# ESPExtra-0_1_1.net
KiCad netlist of a schematic drawn in EAGLE
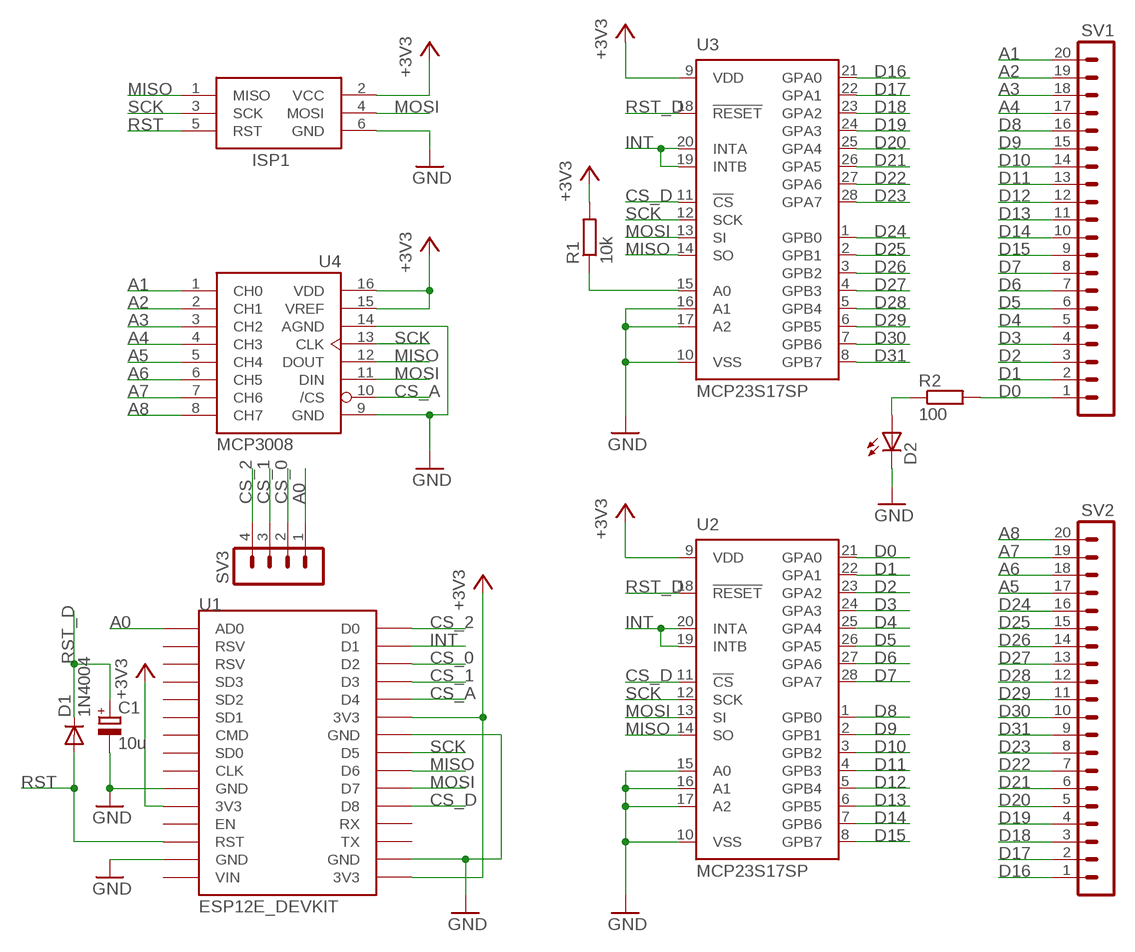
[diagram p0: schematic, sheet 1]

(export (version "E")
  (design (tool "Eeschema 10.0.6"))
  (components
    (comp (ref "C1")
      (value "10u")
      (footprint "eagle-import:E2,5-5")
      (libsource (lib "eagle-import") (part "CPOL-EUE2.5-5"))
    )
    (comp (ref "D1")
      (value "1N4004")
      (footprint "eagle-import:DO41-10")
      (libsource (lib "eagle-import") (part "1N4004"))
    )
    (comp (ref "D2")
      (value "LED3MM")
      (footprint "eagle-import:LED3MM")
      (libsource (lib "eagle-import") (part "LED3MM"))
    )
    (comp (ref "ISP1")
      (value "AVRISP-6")
      (footprint "eagle-import:AVRISP")
      (libsource (lib "eagle-import") (part "AVRISP-6"))
    )
    (comp (ref "R1")
      (value "10k")
      (footprint "eagle-import:0204_5")
      (libsource (lib "eagle-import") (part "R-EU_0204/5"))
    )
    (comp (ref "R2")
      (value "100")
      (footprint "eagle-import:0204_5")
      (libsource (lib "eagle-import") (part "R-EU_0204/5"))
    )
    (comp (ref "SV1")
      (value "MA20-1")
      (footprint "eagle-import:MA20-1")
      (libsource (lib "eagle-import") (part "MA20-1"))
    )
    (comp (ref "SV2")
      (value "MA20-1")
      (footprint "eagle-import:MA20-1")
      (libsource (lib "eagle-import") (part "MA20-1"))
    )
    (comp (ref "SV3")
      (value "MA04-1")
      (footprint "eagle-import:MA04-1")
      (libsource (lib "eagle-import") (part "MA04-1"))
    )
    (comp (ref "U1")
      (value "ESP12E_DEVKIT")
      (footprint "eagle-import:ESP12E_DEVKIT")
      (libsource (lib "eagle-import") (part "ESP12E_DEVKIT"))
    )
    (comp (ref "U2")
      (value "MCP23S17SP")
      (footprint "eagle-import:DIL28-3")
      (fields (field (name "MF") "MICROCHIP") (field (name "MPN") "MCP23S17-E/SP"))
      (libsource (lib "eagle-import") (part "MCP23S17SP"))
    )
    (comp (ref "U3")
      (value "MCP23S17SP")
      (footprint "eagle-import:DIL28-3")
      (fields (field (name "MF") "MICROCHIP") (field (name "MPN") "MCP23S17-E/SP"))
      (libsource (lib "eagle-import") (part "MCP23S17SP"))
    )
    (comp (ref "U4")
      (value "MCP3008")
      (footprint "eagle-import:DIL16")
      (libsource (lib "eagle-import") (part "MCP3008"))
    )
  )
  (nets
    (net (code "1") (name "+3V3") (class "Default")
      (node (ref "ISP1") (pin "2") (pinfunction "VCC_2") (pintype "power_in"))
      (node (ref "R1") (pin "2") (pinfunction "2_2") (pintype "passive"))
      (node (ref "U1") (pin "3V3@0") (pinfunction "3V3_3V3@0") (pintype "bidirectional"))
      (node (ref "U1") (pin "3V3@1") (pinfunction "3V3_3V3@1") (pintype "bidirectional"))
      (node (ref "U1") (pin "3V3@2") (pinfunction "3V3_3V3@2") (pintype "bidirectional"))
      (node (ref "U2") (pin "9") (pinfunction "VDD_9") (pintype "power_in"))
      (node (ref "U3") (pin "9") (pinfunction "VDD_9") (pintype "power_in"))
      (node (ref "U4") (pin "15") (pinfunction "VREF_15") (pintype "input"))
      (node (ref "U4") (pin "16") (pinfunction "VDD_16") (pintype "power_in"))
    )
    (net (code "2") (name "/A0") (class "Default")
      (node (ref "SV3") (pin "1") (pinfunction "1_1") (pintype "passive"))
      (node (ref "U1") (pin "AD0") (pinfunction "AD0_AD0") (pintype "bidirectional"))
    )
    (net (code "3") (name "/A1") (class "Default")
      (node (ref "SV1") (pin "20") (pinfunction "20_20") (pintype "passive"))
      (node (ref "U4") (pin "1") (pinfunction "CH0_1") (pintype "input"))
    )
    (net (code "4") (name "/A2") (class "Default")
      (node (ref "SV1") (pin "19") (pinfunction "19_19") (pintype "passive"))
      (node (ref "U4") (pin "2") (pinfunction "CH1_2") (pintype "input"))
    )
    (net (code "5") (name "/A3") (class "Default")
      (node (ref "SV1") (pin "18") (pinfunction "18_18") (pintype "passive"))
      (node (ref "U4") (pin "3") (pinfunction "CH2_3") (pintype "input"))
    )
    (net (code "6") (name "/A4") (class "Default")
      (node (ref "SV1") (pin "17") (pinfunction "17_17") (pintype "passive"))
      (node (ref "U4") (pin "4") (pinfunction "CH3_4") (pintype "input"))
    )
    (net (code "7") (name "/A5") (class "Default")
      (node (ref "SV2") (pin "17") (pinfunction "17_17") (pintype "passive"))
      (node (ref "U4") (pin "5") (pinfunction "CH4_5") (pintype "input"))
    )
    (net (code "8") (name "/A6") (class "Default")
      (node (ref "SV2") (pin "18") (pinfunction "18_18") (pintype "passive"))
      (node (ref "U4") (pin "6") (pinfunction "CH5_6") (pintype "input"))
    )
    (net (code "9") (name "/A7") (class "Default")
      (node (ref "SV2") (pin "19") (pinfunction "19_19") (pintype "passive"))
      (node (ref "U4") (pin "7") (pinfunction "CH6_7") (pintype "input"))
    )
    (net (code "10") (name "/A8") (class "Default")
      (node (ref "SV2") (pin "20") (pinfunction "20_20") (pintype "passive"))
      (node (ref "U4") (pin "8") (pinfunction "CH7_8") (pintype "input"))
    )
    (net (code "11") (name "/CS_0") (class "Default")
      (node (ref "SV3") (pin "2") (pinfunction "2_2") (pintype "passive"))
      (node (ref "U1") (pin "D2") (pinfunction "D2_D2") (pintype "bidirectional"))
    )
    (net (code "12") (name "/CS_1") (class "Default")
      (node (ref "SV3") (pin "3") (pinfunction "3_3") (pintype "passive"))
      (node (ref "U1") (pin "D3") (pinfunction "D3_D3") (pintype "bidirectional"))
    )
    (net (code "13") (name "/CS_2") (class "Default")
      (node (ref "SV3") (pin "4") (pinfunction "4_4") (pintype "passive"))
      (node (ref "U1") (pin "D0") (pinfunction "D0_D0") (pintype "bidirectional"))
    )
    (net (code "14") (name "/CS_A") (class "Default")
      (node (ref "U1") (pin "D4") (pinfunction "D4_D4") (pintype "bidirectional"))
      (node (ref "U4") (pin "10") (pinfunction "/CS_10") (pintype "input"))
    )
    (net (code "15") (name "/CS_D") (class "Default")
      (node (ref "U1") (pin "D8") (pinfunction "D8_D8") (pintype "bidirectional"))
      (node (ref "U2") (pin "11") (pinfunction "~{CS}_11") (pintype "input"))
      (node (ref "U3") (pin "11") (pinfunction "~{CS}_11") (pintype "input"))
    )
    (net (code "16") (name "/D0") (class "Default")
      (node (ref "R2") (pin "2") (pinfunction "2_2") (pintype "passive"))
      (node (ref "SV1") (pin "1") (pinfunction "1_1") (pintype "passive"))
      (node (ref "U2") (pin "21") (pinfunction "GPA0_21") (pintype "bidirectional"))
    )
    (net (code "17") (name "/D1") (class "Default")
      (node (ref "SV1") (pin "2") (pinfunction "2_2") (pintype "passive"))
      (node (ref "U2") (pin "22") (pinfunction "GPA1_22") (pintype "bidirectional"))
    )
    (net (code "18") (name "/D2") (class "Default")
      (node (ref "SV1") (pin "3") (pinfunction "3_3") (pintype "passive"))
      (node (ref "U2") (pin "23") (pinfunction "GPA2_23") (pintype "bidirectional"))
    )
    (net (code "19") (name "/D3") (class "Default")
      (node (ref "SV1") (pin "4") (pinfunction "4_4") (pintype "passive"))
      (node (ref "U2") (pin "24") (pinfunction "GPA3_24") (pintype "bidirectional"))
    )
    (net (code "20") (name "/D4") (class "Default")
      (node (ref "SV1") (pin "5") (pinfunction "5_5") (pintype "passive"))
      (node (ref "U2") (pin "25") (pinfunction "GPA4_25") (pintype "bidirectional"))
    )
    (net (code "21") (name "/D5") (class "Default")
      (node (ref "SV1") (pin "6") (pinfunction "6_6") (pintype "passive"))
      (node (ref "U2") (pin "26") (pinfunction "GPA5_26") (pintype "bidirectional"))
    )
    (net (code "22") (name "/D6") (class "Default")
      (node (ref "SV1") (pin "7") (pinfunction "7_7") (pintype "passive"))
      (node (ref "U2") (pin "27") (pinfunction "GPA6_27") (pintype "bidirectional"))
    )
    (net (code "23") (name "/D7") (class "Default")
      (node (ref "SV1") (pin "8") (pinfunction "8_8") (pintype "passive"))
      (node (ref "U2") (pin "28") (pinfunction "GPA7_28") (pintype "bidirectional"))
    )
    (net (code "24") (name "/D8") (class "Default")
      (node (ref "SV1") (pin "16") (pinfunction "16_16") (pintype "passive"))
      (node (ref "U2") (pin "1") (pinfunction "GPB0_1") (pintype "bidirectional"))
    )
    (net (code "25") (name "/D9") (class "Default")
      (node (ref "SV1") (pin "15") (pinfunction "15_15") (pintype "passive"))
      (node (ref "U2") (pin "2") (pinfunction "GPB1_2") (pintype "bidirectional"))
    )
    (net (code "26") (name "/D10") (class "Default")
      (node (ref "SV1") (pin "14") (pinfunction "14_14") (pintype "passive"))
      (node (ref "U2") (pin "3") (pinfunction "GPB2_3") (pintype "bidirectional"))
    )
    (net (code "27") (name "/D11") (class "Default")
      (node (ref "SV1") (pin "13") (pinfunction "13_13") (pintype "passive"))
      (node (ref "U2") (pin "4") (pinfunction "GPB3_4") (pintype "bidirectional"))
    )
    (net (code "28") (name "/D12") (class "Default")
      (node (ref "SV1") (pin "12") (pinfunction "12_12") (pintype "passive"))
      (node (ref "U2") (pin "5") (pinfunction "GPB4_5") (pintype "bidirectional"))
    )
    (net (code "29") (name "/D13") (class "Default")
      (node (ref "SV1") (pin "11") (pinfunction "11_11") (pintype "passive"))
      (node (ref "U2") (pin "6") (pinfunction "GPB5_6") (pintype "bidirectional"))
    )
    (net (code "30") (name "/D14") (class "Default")
      (node (ref "SV1") (pin "10") (pinfunction "10_10") (pintype "passive"))
      (node (ref "U2") (pin "7") (pinfunction "GPB6_7") (pintype "bidirectional"))
    )
    (net (code "31") (name "/D15") (class "Default")
      (node (ref "SV1") (pin "9") (pinfunction "9_9") (pintype "passive"))
      (node (ref "U2") (pin "8") (pinfunction "GPB7_8") (pintype "bidirectional"))
    )
    (net (code "32") (name "/D16") (class "Default")
      (node (ref "SV2") (pin "1") (pinfunction "1_1") (pintype "passive"))
      (node (ref "U3") (pin "21") (pinfunction "GPA0_21") (pintype "bidirectional"))
    )
    (net (code "33") (name "/D17") (class "Default")
      (node (ref "SV2") (pin "2") (pinfunction "2_2") (pintype "passive"))
      (node (ref "U3") (pin "22") (pinfunction "GPA1_22") (pintype "bidirectional"))
    )
    (net (code "34") (name "/D18") (class "Default")
      (node (ref "SV2") (pin "3") (pinfunction "3_3") (pintype "passive"))
      (node (ref "U3") (pin "23") (pinfunction "GPA2_23") (pintype "bidirectional"))
    )
    (net (code "35") (name "/D19") (class "Default")
      (node (ref "SV2") (pin "4") (pinfunction "4_4") (pintype "passive"))
      (node (ref "U3") (pin "24") (pinfunction "GPA3_24") (pintype "bidirectional"))
    )
    (net (code "36") (name "/D20") (class "Default")
      (node (ref "SV2") (pin "5") (pinfunction "5_5") (pintype "passive"))
      (node (ref "U3") (pin "25") (pinfunction "GPA4_25") (pintype "bidirectional"))
    )
    (net (code "37") (name "/D21") (class "Default")
      (node (ref "SV2") (pin "6") (pinfunction "6_6") (pintype "passive"))
      (node (ref "U3") (pin "26") (pinfunction "GPA5_26") (pintype "bidirectional"))
    )
    (net (code "38") (name "/D22") (class "Default")
      (node (ref "SV2") (pin "7") (pinfunction "7_7") (pintype "passive"))
      (node (ref "U3") (pin "27") (pinfunction "GPA6_27") (pintype "bidirectional"))
    )
    (net (code "39") (name "/D23") (class "Default")
      (node (ref "SV2") (pin "8") (pinfunction "8_8") (pintype "passive"))
      (node (ref "U3") (pin "28") (pinfunction "GPA7_28") (pintype "bidirectional"))
    )
    (net (code "40") (name "/D24") (class "Default")
      (node (ref "SV2") (pin "16") (pinfunction "16_16") (pintype "passive"))
      (node (ref "U3") (pin "1") (pinfunction "GPB0_1") (pintype "bidirectional"))
    )
    (net (code "41") (name "/D25") (class "Default")
      (node (ref "SV2") (pin "15") (pinfunction "15_15") (pintype "passive"))
      (node (ref "U3") (pin "2") (pinfunction "GPB1_2") (pintype "bidirectional"))
    )
    (net (code "42") (name "/D26") (class "Default")
      (node (ref "SV2") (pin "14") (pinfunction "14_14") (pintype "passive"))
      (node (ref "U3") (pin "3") (pinfunction "GPB2_3") (pintype "bidirectional"))
    )
    (net (code "43") (name "/D27") (class "Default")
      (node (ref "SV2") (pin "13") (pinfunction "13_13") (pintype "passive"))
      (node (ref "U3") (pin "4") (pinfunction "GPB3_4") (pintype "bidirectional"))
    )
    (net (code "44") (name "/D28") (class "Default")
      (node (ref "SV2") (pin "12") (pinfunction "12_12") (pintype "passive"))
      (node (ref "U3") (pin "5") (pinfunction "GPB4_5") (pintype "bidirectional"))
    )
    (net (code "45") (name "/D29") (class "Default")
      (node (ref "SV2") (pin "11") (pinfunction "11_11") (pintype "passive"))
      (node (ref "U3") (pin "6") (pinfunction "GPB5_6") (pintype "bidirectional"))
    )
    (net (code "46") (name "/D30") (class "Default")
      (node (ref "SV2") (pin "10") (pinfunction "10_10") (pintype "passive"))
      (node (ref "U3") (pin "7") (pinfunction "GPB6_7") (pintype "bidirectional"))
    )
    (net (code "47") (name "/D31") (class "Default")
      (node (ref "SV2") (pin "9") (pinfunction "9_9") (pintype "passive"))
      (node (ref "U3") (pin "8") (pinfunction "GPB7_8") (pintype "bidirectional"))
    )
    (net (code "48") (name "/INT") (class "Default")
      (node (ref "U1") (pin "D1") (pinfunction "D1_D1") (pintype "bidirectional"))
      (node (ref "U2") (pin "19") (pinfunction "INTB_19") (pintype "output"))
      (node (ref "U2") (pin "20") (pinfunction "INTA_20") (pintype "output"))
      (node (ref "U3") (pin "19") (pinfunction "INTB_19") (pintype "output"))
      (node (ref "U3") (pin "20") (pinfunction "INTA_20") (pintype "output"))
    )
    (net (code "49") (name "/MISO") (class "Default")
      (node (ref "ISP1") (pin "1") (pinfunction "MISO_1") (pintype "input"))
      (node (ref "U1") (pin "D6") (pinfunction "D6_D6") (pintype "bidirectional"))
      (node (ref "U2") (pin "14") (pinfunction "SO_14") (pintype "output"))
      (node (ref "U3") (pin "14") (pinfunction "SO_14") (pintype "output"))
      (node (ref "U4") (pin "12") (pinfunction "DOUT_12") (pintype "output"))
    )
    (net (code "50") (name "/MOSI") (class "Default")
      (node (ref "ISP1") (pin "4") (pinfunction "MOSI_4") (pintype "output"))
      (node (ref "U1") (pin "D7") (pinfunction "D7_D7") (pintype "bidirectional"))
      (node (ref "U2") (pin "13") (pinfunction "SI_13") (pintype "input"))
      (node (ref "U3") (pin "13") (pinfunction "SI_13") (pintype "input"))
      (node (ref "U4") (pin "11") (pinfunction "DIN_11") (pintype "input"))
    )
    (net (code "51") (name "/RST") (class "Default")
      (node (ref "D1") (pin "A") (pinfunction "A_A") (pintype "passive"))
      (node (ref "ISP1") (pin "5") (pinfunction "RST_5") (pintype "output"))
      (node (ref "U1") (pin "RST") (pinfunction "RST_RST") (pintype "bidirectional"))
    )
    (net (code "52") (name "/RST_D") (class "Default")
      (node (ref "C1") (pin "+") (pinfunction "+_+") (pintype "passive"))
      (node (ref "D1") (pin "C") (pinfunction "C_C") (pintype "passive"))
      (node (ref "U2") (pin "18") (pinfunction "~{RESET}_18") (pintype "input"))
      (node (ref "U3") (pin "18") (pinfunction "~{RESET}_18") (pintype "input"))
    )
    (net (code "53") (name "/SCK") (class "Default")
      (node (ref "ISP1") (pin "3") (pinfunction "SCK_3") (pintype "output"))
      (node (ref "U1") (pin "D5") (pinfunction "D5_D5") (pintype "bidirectional"))
      (node (ref "U2") (pin "12") (pinfunction "SCK_12") (pintype "input"))
      (node (ref "U3") (pin "12") (pinfunction "SCK_12") (pintype "input"))
      (node (ref "U4") (pin "13") (pinfunction "CLK_13") (pintype "input"))
    )
    (net (code "54") (name "GND") (class "Default")
      (node (ref "C1") (pin "-") (pinfunction "-_-") (pintype "passive"))
      (node (ref "D2") (pin "K") (pinfunction "C_K") (pintype "passive"))
      (node (ref "ISP1") (pin "6") (pinfunction "GND_6") (pintype "power_in"))
      (node (ref "U1") (pin "GND@0") (pinfunction "GND_GND@0") (pintype "bidirectional"))
      (node (ref "U1") (pin "GND@1") (pinfunction "GND_GND@1") (pintype "bidirectional"))
      (node (ref "U1") (pin "GND@2") (pinfunction "GND_GND@2") (pintype "bidirectional"))
      (node (ref "U1") (pin "GND@3") (pinfunction "GND_GND@3") (pintype "bidirectional"))
      (node (ref "U2") (pin "10") (pinfunction "VSS_10") (pintype "power_in"))
      (node (ref "U2") (pin "15") (pinfunction "A0_15") (pintype "input"))
      (node (ref "U2") (pin "16") (pinfunction "A1_16") (pintype "input"))
      (node (ref "U2") (pin "17") (pinfunction "A2_17") (pintype "input"))
      (node (ref "U3") (pin "10") (pinfunction "VSS_10") (pintype "power_in"))
      (node (ref "U3") (pin "16") (pinfunction "A1_16") (pintype "input"))
      (node (ref "U3") (pin "17") (pinfunction "A2_17") (pintype "input"))
      (node (ref "U4") (pin "14") (pinfunction "AGND_14") (pintype "power_in"))
      (node (ref "U4") (pin "9") (pinfunction "GND_9") (pintype "power_in"))
    )
    (net (code "55") (name "Net-(D2-PadA)") (class "Default")
      (node (ref "D2") (pin "A") (pinfunction "A_A") (pintype "passive"))
      (node (ref "R2") (pin "1") (pinfunction "1_1") (pintype "passive"))
    )
    (net (code "56") (name "Net-(U3-A0)") (class "Default")
      (node (ref "R1") (pin "1") (pinfunction "1_1") (pintype "passive"))
      (node (ref "U3") (pin "15") (pinfunction "A0_15") (pintype "input"))
    )
    (net (code "57") (name "unconnected-(U1-PadCLK)") (class "Default")
      (node (ref "U1") (pin "CLK") (pinfunction "CLK_CLK") (pintype "bidirectional"))
    )
    (net (code "58") (name "unconnected-(U1-PadCMD)") (class "Default")
      (node (ref "U1") (pin "CMD") (pinfunction "CMD_CMD") (pintype "bidirectional"))
    )
    (net (code "59") (name "unconnected-(U1-PadEN)") (class "Default")
      (node (ref "U1") (pin "EN") (pinfunction "EN_EN") (pintype "bidirectional"))
    )
    (net (code "60") (name "unconnected-(U1-PadRX)") (class "Default")
      (node (ref "U1") (pin "RX") (pinfunction "RX_RX") (pintype "bidirectional"))
    )
    (net (code "61") (name "unconnected-(U1-PadSD0)") (class "Default")
      (node (ref "U1") (pin "SD0") (pinfunction "SD0_SD0") (pintype "bidirectional"))
    )
    (net (code "62") (name "unconnected-(U1-PadSD1)") (class "Default")
      (node (ref "U1") (pin "SD1") (pinfunction "SD1_SD1") (pintype "bidirectional"))
    )
    (net (code "63") (name "unconnected-(U1-PadSD2)") (class "Default")
      (node (ref "U1") (pin "SD2") (pinfunction "SD2_SD2") (pintype "bidirectional"))
    )
    (net (code "64") (name "unconnected-(U1-PadSD3)") (class "Default")
      (node (ref "U1") (pin "SD3") (pinfunction "SD3_SD3") (pintype "bidirectional"))
    )
    (net (code "65") (name "unconnected-(U1-PadTX)") (class "Default")
      (node (ref "U1") (pin "TX") (pinfunction "TX_TX") (pintype "bidirectional"))
    )
    (net (code "66") (name "unconnected-(U1-PadVIN)") (class "Default")
      (node (ref "U1") (pin "VIN") (pinfunction "VIN_VIN") (pintype "bidirectional"))
    )
    (net (code "67") (name "unconnected-(U1-RSV-PadRSV@0)") (class "Default")
      (node (ref "U1") (pin "RSV@0") (pinfunction "RSV_RSV@0") (pintype "bidirectional"))
    )
    (net (code "68") (name "unconnected-(U1-RSV-PadRSV@1)") (class "Default")
      (node (ref "U1") (pin "RSV@1") (pinfunction "RSV_RSV@1") (pintype "bidirectional"))
    )
  )
)
